# design.net
KiCad netlist of a schematic drawn in EasyEDA Pro
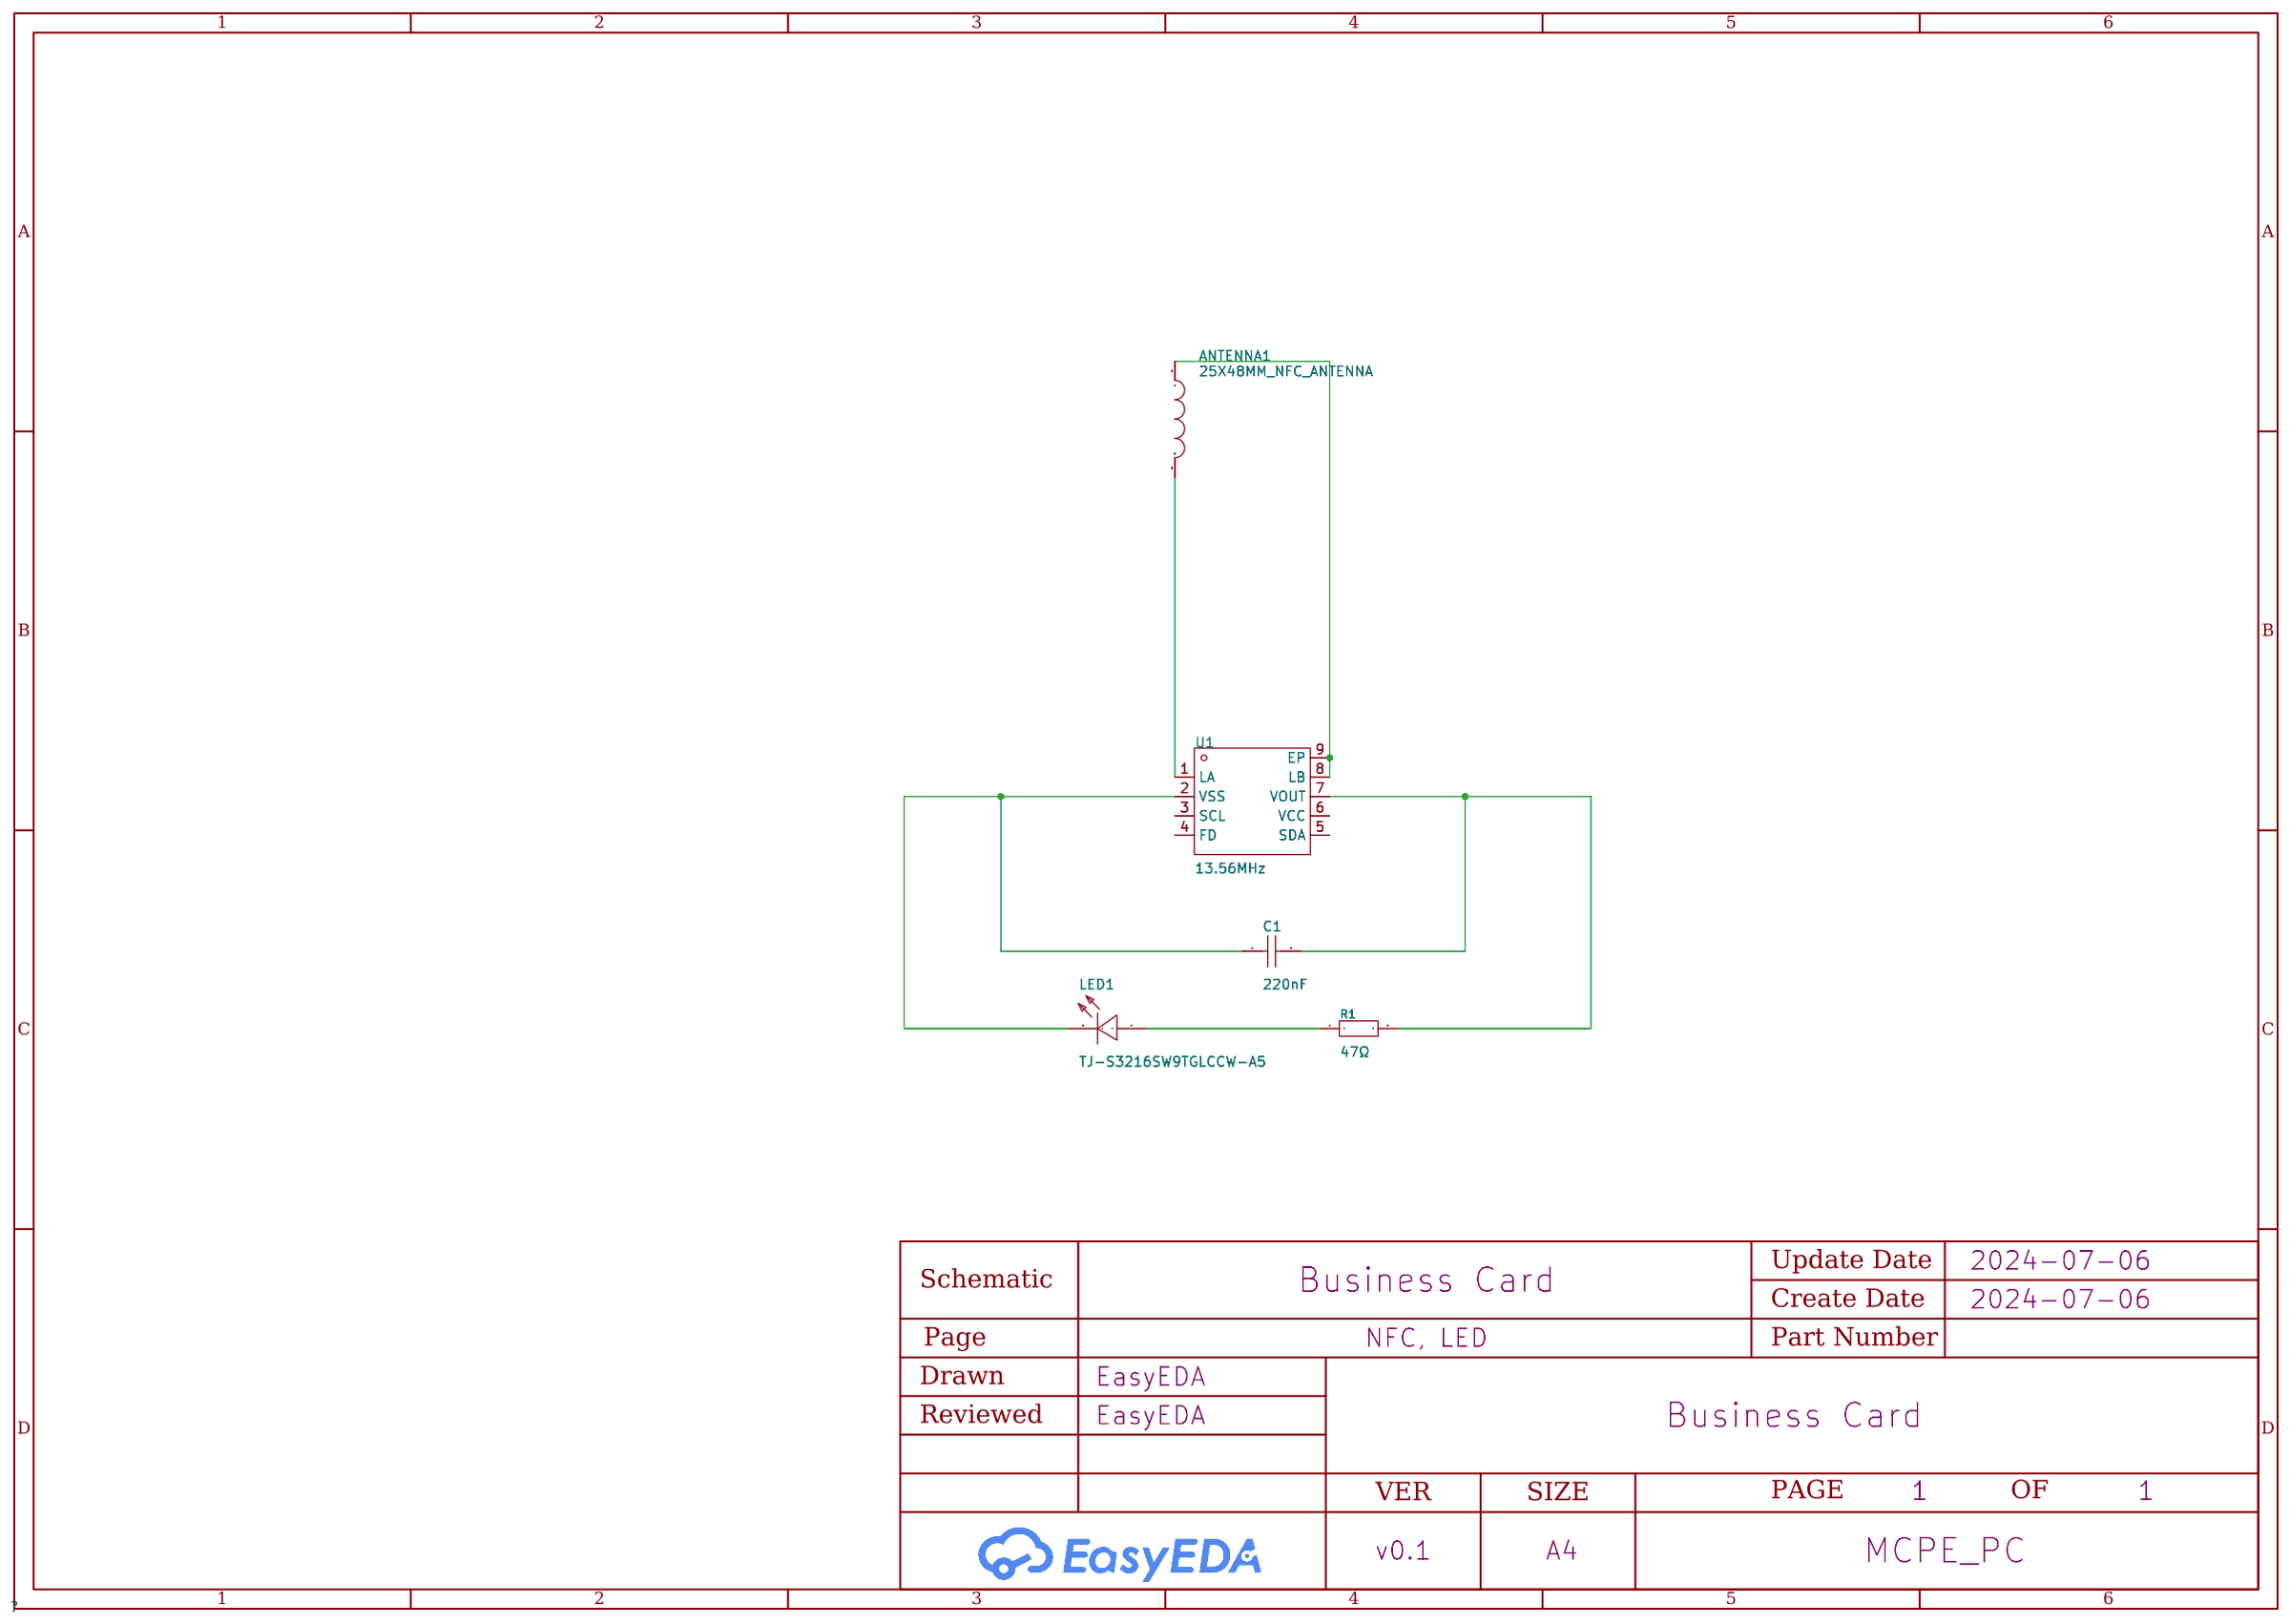
[diagram p0: schematic sheet]

(export (version "E")
  (design (tool "Eeschema 10.0.6"))
  (components
    (comp (ref "ANTENNA1")
      (value "25X48MM_NFC_ANTENNA")
      (libsource (lib "easyedapro") (part "25X48MM_NFC_ANTENNA"))
    )
    (comp (ref "C1")
      (value "220nF")
      (footprint "easyedapro:C0603")
      (fields
        (field (name "Manufacturer Part") "CL10B224KA8NNNC")
        (field (name "Manufacturer") "SAMSUNG(三星)")
      )
      (libsource (lib "easyedapro") (part "CL10B224KA8NNNC"))
    )
    (comp (ref "LED1")
      (value "TJ-S3216SW9TGLCCW-A5")
      (footprint "easyedapro:LED1206-R-RD_WHITE")
      (fields (field (name "Manufacturer") "TOGIALED(统佳)"))
      (libsource (lib "easyedapro") (part "TJ-S3216SW9TGLCCW-A5"))
    )
    (comp (ref "R1")
      (value "47Ω")
      (footprint "easyedapro:R0603")
      (fields
        (field (name "Manufacturer Part") "0603WAF470JT5E")
        (field (name "Manufacturer") "UNI-ROYAL(厚声)")
      )
      (libsource (lib "easyedapro") (part "0603WAF470JT5E"))
    )
    (comp (ref "U1")
      (value "13.56MHz")
      (footprint "easyedapro:XQFN-8_L1.6-W1.6-P0.50-BL")
      (fields (field (name "Manufacturer Part") "NT3H2111W0FHKH") (field (name "Manufacturer") "NXP(恩智浦)"))
      (libsource (lib "easyedapro") (part "NT3H2111W0FHKH"))
    )
  )
  (nets
    (net (code "1") (name "Net-(LED1-A)") (class "Default")
      (node (ref "LED1") (pin "1") (pinfunction "A_1") (pintype "unspecified"))
      (node (ref "R1") (pin "1") (pinfunction "1_1") (pintype "input"))
    )
    (net (code "2") (name "Net-(LED1-K)") (class "Default")
      (node (ref "C1") (pin "1") (pinfunction "1_1") (pintype "input"))
      (node (ref "LED1") (pin "2") (pinfunction "K_2") (pintype "unspecified"))
      (node (ref "U1") (pin "2") (pinfunction "VSS_2") (pintype "unspecified"))
    )
    (net (code "3") (name "Net-(U1-EP)") (class "Default")
      (node (ref "ANTENNA1") (pin "P$1") (pinfunction "P$1_P$1") (pintype "bidirectional"))
      (node (ref "U1") (pin "8") (pinfunction "LB_8") (pintype "unspecified"))
      (node (ref "U1") (pin "9") (pinfunction "EP_9") (pintype "unspecified"))
    )
    (net (code "4") (name "Net-(U1-LA)") (class "Default")
      (node (ref "ANTENNA1") (pin "P$2") (pinfunction "P$2_P$2") (pintype "bidirectional"))
      (node (ref "U1") (pin "1") (pinfunction "LA_1") (pintype "unspecified"))
    )
    (net (code "5") (name "Net-(U1-VOUT)") (class "Default")
      (node (ref "C1") (pin "2") (pinfunction "2_2") (pintype "input"))
      (node (ref "R1") (pin "2") (pinfunction "2_2") (pintype "input"))
      (node (ref "U1") (pin "7") (pinfunction "VOUT_7") (pintype "unspecified"))
    )
    (net (code "6") (name "unconnected-(U1-FD-Pad4)") (class "Default")
      (node (ref "U1") (pin "4") (pinfunction "FD_4") (pintype "unspecified"))
    )
    (net (code "7") (name "unconnected-(U1-SCL-Pad3)") (class "Default")
      (node (ref "U1") (pin "3") (pinfunction "SCL_3") (pintype "unspecified"))
    )
    (net (code "8") (name "unconnected-(U1-SDA-Pad5)") (class "Default")
      (node (ref "U1") (pin "5") (pinfunction "SDA_5") (pintype "unspecified"))
    )
    (net (code "9") (name "unconnected-(U1-VCC-Pad6)") (class "Default")
      (node (ref "U1") (pin "6") (pinfunction "VCC_6") (pintype "unspecified"))
    )
  )
)
